# button_brick_smd.net
KiCad netlist of a schematic drawn in EAGLE
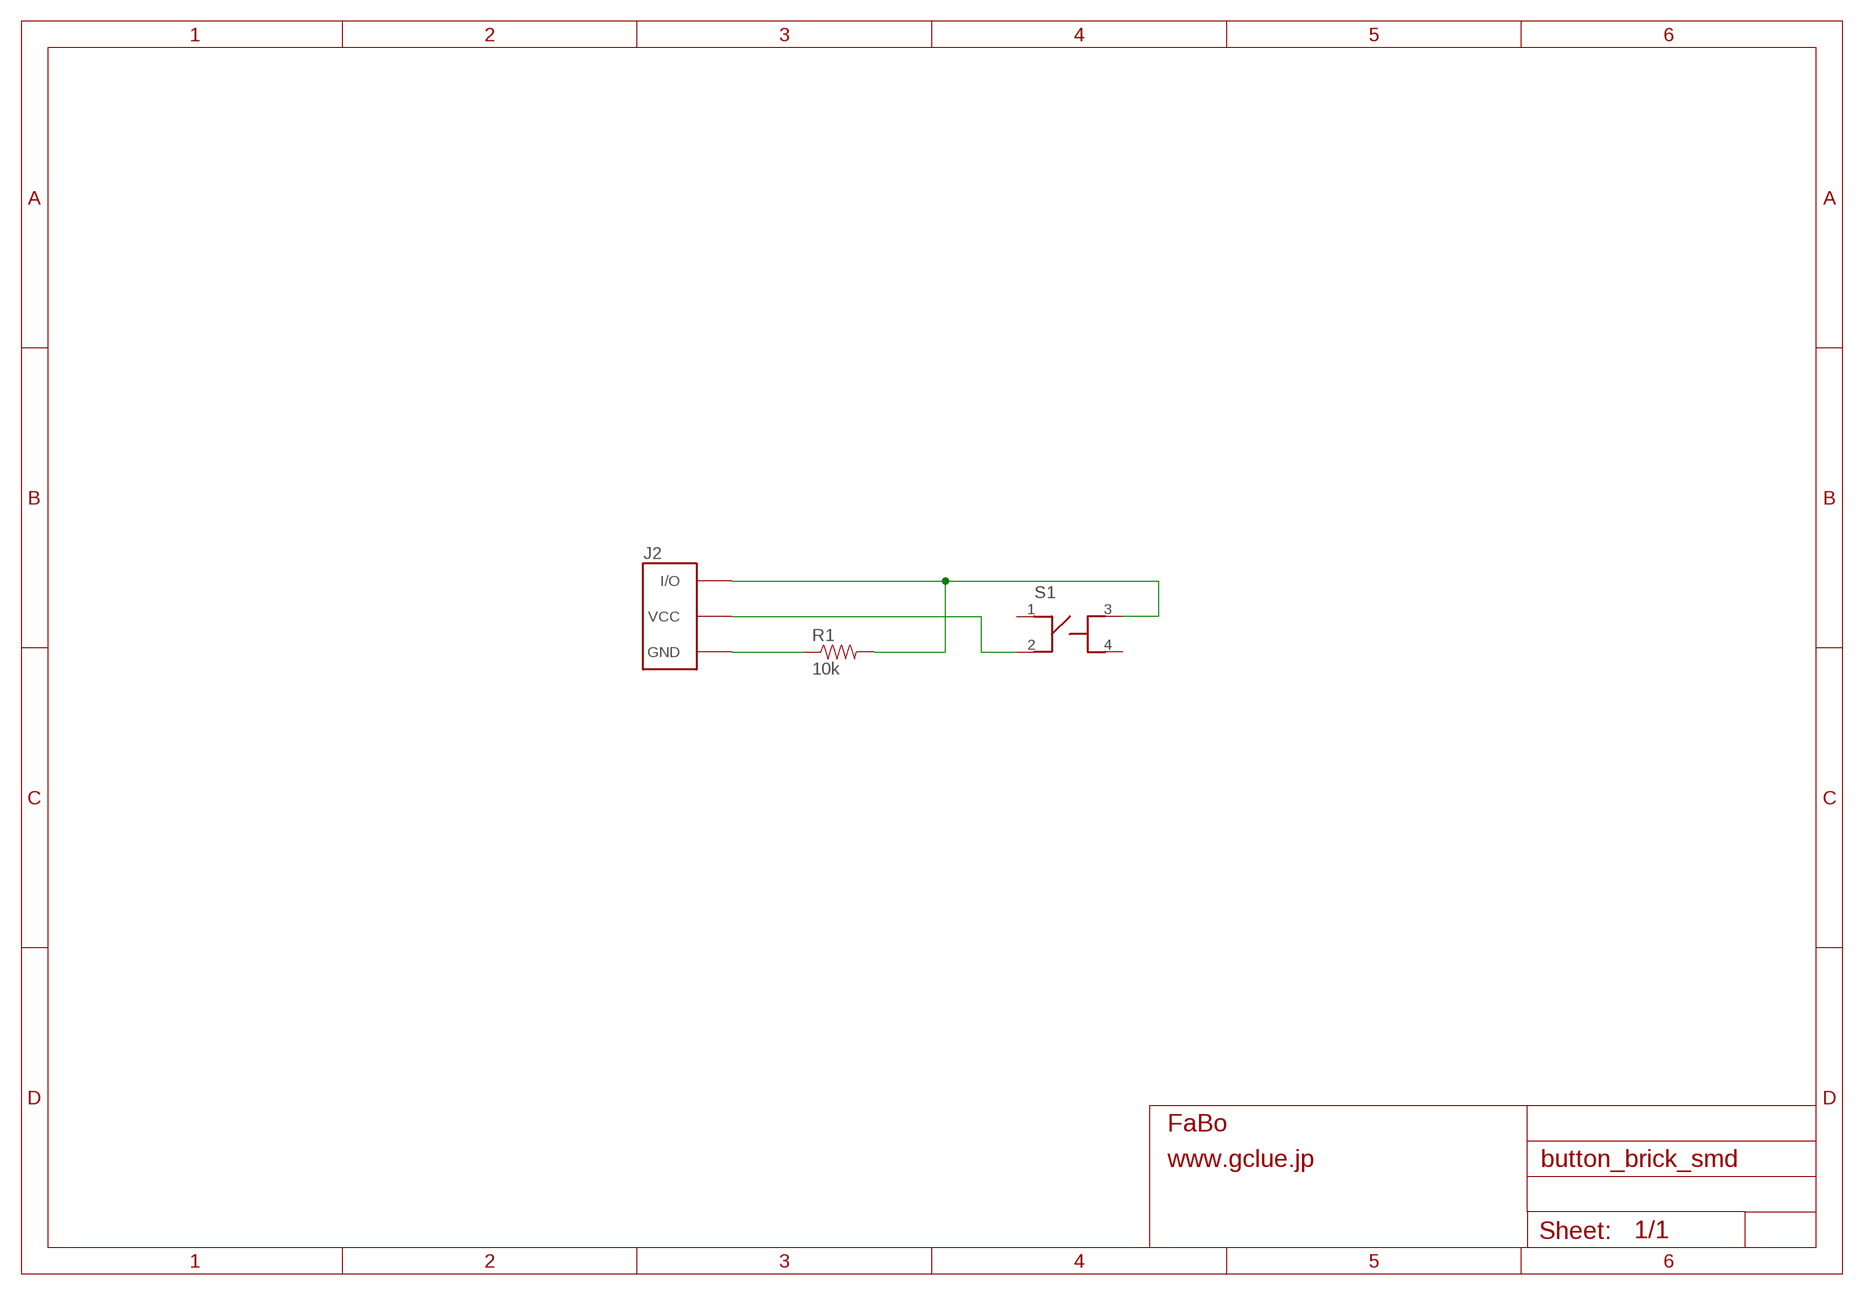
[diagram p0: schematic, sheet 1]

(export (version "E")
  (design (tool "Eeschema 10.0.6"))
  (components
    (comp (ref "J2")
      (value "BRICK_3PIN")
      (footprint "eagle-import:BRICK_3PIN")
      (libsource (lib "eagle-import") (part "BRICK_3PIN"))
    )
    (comp (ref "R1")
      (value "10k")
      (footprint "eagle-import:0603-RES")
      (libsource (lib "eagle-import") (part "RESISTOR0603"))
    )
    (comp (ref "S1")
      (value "SWITCH-LS6J2M-T")
      (footprint "eagle-import:SWITCH-LS6J2M-T")
      (libsource (lib "eagle-import") (part "SWITCH-LS6J2M-T"))
    )
  )
  (nets
    (net (code "1") (name "Net-(J2-I{slash}O)") (class "Default")
      (node (ref "J2") (pin "IN/OUT") (pinfunction "I/O_IN/OUT") (pintype "bidirectional"))
      (node (ref "R1") (pin "2") (pinfunction "2_2") (pintype "passive"))
      (node (ref "S1") (pin "3") (pinfunction "3_3") (pintype "bidirectional"))
    )
    (net (code "2") (name "Net-(J2-PadGND)") (class "Default")
      (node (ref "J2") (pin "GND") (pinfunction "GND_GND") (pintype "bidirectional"))
      (node (ref "R1") (pin "1") (pinfunction "1_1") (pintype "passive"))
    )
    (net (code "3") (name "Net-(J2-PadVCC)") (class "Default")
      (node (ref "J2") (pin "VCC") (pinfunction "VCC_VCC") (pintype "bidirectional"))
      (node (ref "S1") (pin "2") (pinfunction "2_2") (pintype "bidirectional"))
    )
    (net (code "4") (name "unconnected-(S1-Pad1)") (class "Default")
      (node (ref "S1") (pin "1") (pinfunction "1_1") (pintype "bidirectional"))
    )
    (net (code "5") (name "unconnected-(S1-Pad4)") (class "Default")
      (node (ref "S1") (pin "4") (pinfunction "4_4") (pintype "bidirectional"))
    )
  )
)
